# POWER.net
KiCad netlist of a schematic drawn in Altium Designer
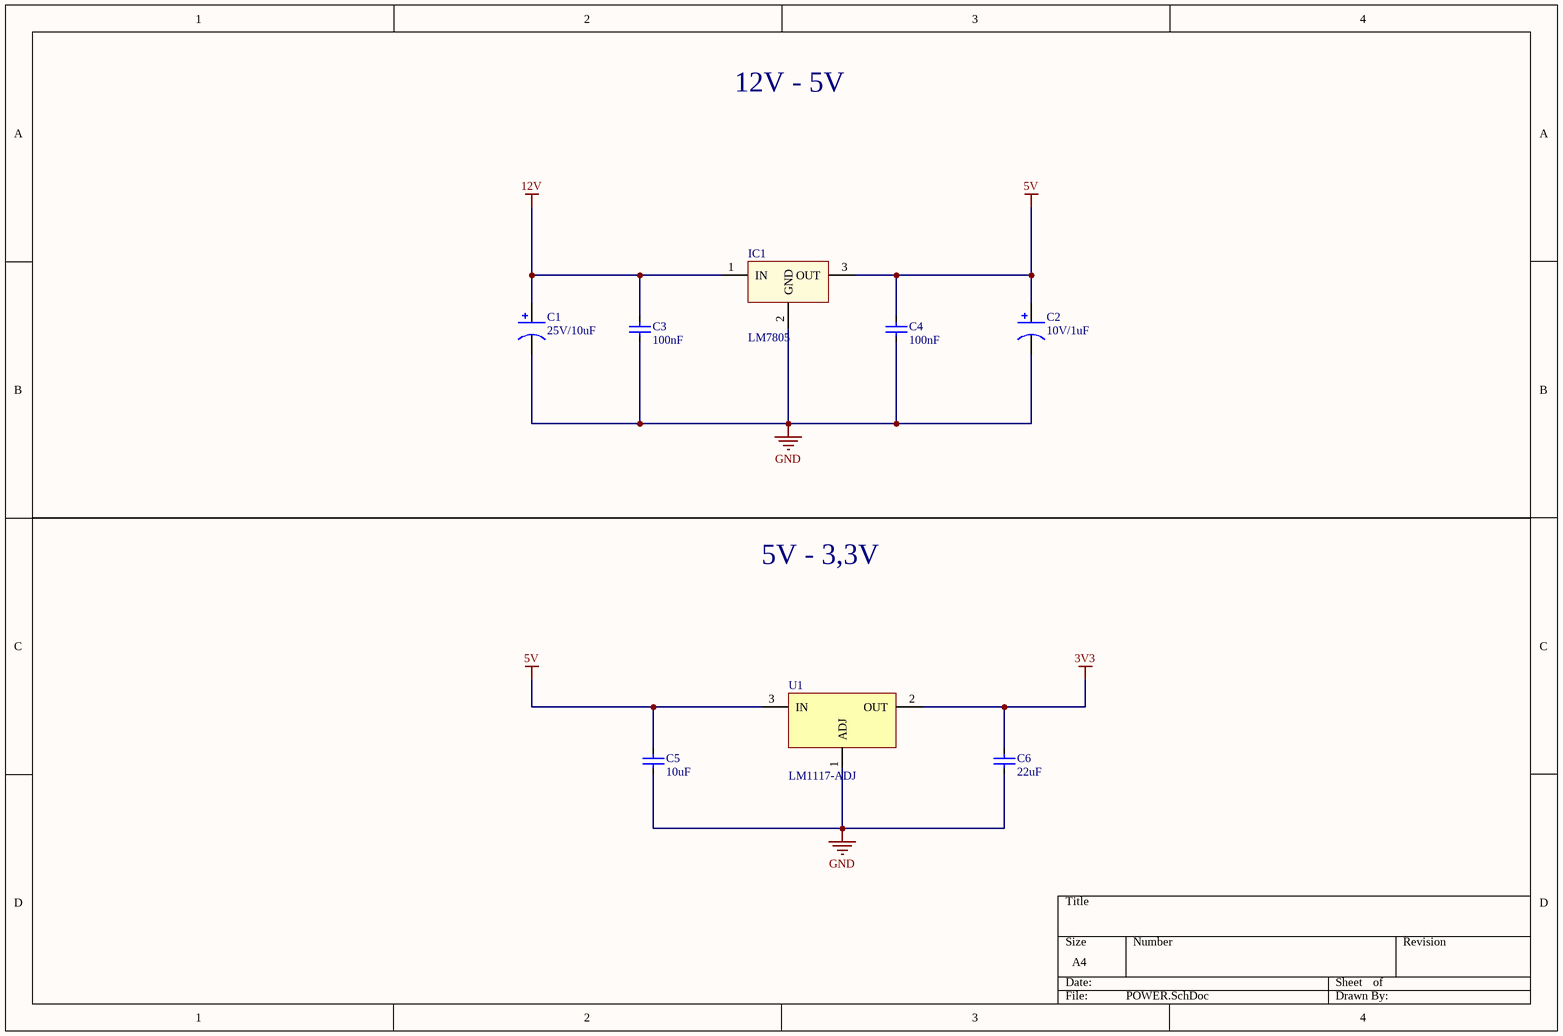
[diagram p0: POWER.SchDoc]

(export (version "E")
  (design (tool "Eeschema 10.0.6"))
  (components
    (comp (ref "C1")
      (value "25V/10uF")
      (footprint "C3MM")
      (description "Polarized Capacitor (Axial)")
      (fields (field (name "PUBLISHER") "Altium Limited"))
      (libsource (lib "Main") (part "Cap Pol"))
    )
    (comp (ref "C2")
      (value "10V/1uF")
      (footprint "C3MM")
      (description "Polarized Capacitor (Axial)")
      (fields (field (name "PUBLISHER") "Altium Limited"))
      (libsource (lib "Main") (part "Cap Pol"))
    )
    (comp (ref "C3")
      (value "100nF")
      (footprint "CAP_0805")
      (description "Capacitor")
      (fields (field (name "PUBLISHER") "Altium Limited"))
      (libsource (lib "Main") (part "CapSMD"))
    )
    (comp (ref "C4")
      (value "100nF")
      (footprint "CAP_0805")
      (description "Capacitor")
      (fields (field (name "PUBLISHER") "Altium Limited"))
      (libsource (lib "Main") (part "CapSMD"))
    )
    (comp (ref "C5")
      (value "10uF")
      (footprint "CAP_0805")
      (description "Capacitor")
      (fields (field (name "PUBLISHER") "Altium Limited"))
      (libsource (lib "Main") (part "CapSMD"))
    )
    (comp (ref "C6")
      (value "22uF")
      (footprint "CAP_0805")
      (description "Capacitor")
      (fields (field (name "PUBLISHER") "Altium Limited"))
      (libsource (lib "Main") (part "CapSMD"))
    )
    (comp (ref "IC1")
      (value "LM7805")
      (footprint "QTO-220")
      (description "On ap +, from + 5 to + 24VDC")
      (libsource (lib "Main") (part "LM78xx"))
    )
    (comp (ref "U1")
      (value "LM1117-ADJ")
      (footprint "LM1117-SOP")
      (description "800mA Low-Dropout Linear Regulator")
      (fields (field (name "CREATOR") "Nguyen Ba Bien"))
      (libsource (lib "Main") (part "LM1117-ADJ"))
    )
  )
  (nets
    (net (code "1") (name "3V3") (class "Default")
      (node (ref "C6") (pin "1") (pinfunction "1_1") (pintype "passive"))
      (node (ref "U1") (pin "2") (pinfunction "OUT_2") (pintype "passive"))
    )
    (net (code "2") (name "5V") (class "Default")
      (node (ref "C2") (pin "1") (pinfunction "1_1") (pintype "passive"))
      (node (ref "C4") (pin "1") (pinfunction "1_1") (pintype "passive"))
      (node (ref "C5") (pin "1") (pinfunction "1_1") (pintype "passive"))
      (node (ref "IC1") (pin "3") (pinfunction "OUT_3") (pintype "passive"))
      (node (ref "U1") (pin "3") (pinfunction "IN_3") (pintype "passive"))
    )
    (net (code "3") (name "12V") (class "Default")
      (node (ref "C1") (pin "1") (pinfunction "1_1") (pintype "passive"))
      (node (ref "C3") (pin "1") (pinfunction "1_1") (pintype "passive"))
      (node (ref "IC1") (pin "1") (pinfunction "IN_1") (pintype "passive"))
    )
    (net (code "4") (name "GND") (class "Default")
      (node (ref "C1") (pin "2") (pinfunction "2_2") (pintype "passive"))
      (node (ref "C2") (pin "2") (pinfunction "2_2") (pintype "passive"))
      (node (ref "C3") (pin "2") (pinfunction "2_2") (pintype "passive"))
      (node (ref "C4") (pin "2") (pinfunction "2_2") (pintype "passive"))
      (node (ref "C5") (pin "2") (pinfunction "2_2") (pintype "passive"))
      (node (ref "C6") (pin "2") (pinfunction "2_2") (pintype "passive"))
      (node (ref "IC1") (pin "2") (pinfunction "GND_2") (pintype "passive"))
      (node (ref "U1") (pin "1") (pinfunction "ADJ_1") (pintype "passive"))
    )
  )
)
